# DEGREE_V1_1.net
KiCad netlist of a schematic drawn in EAGLE
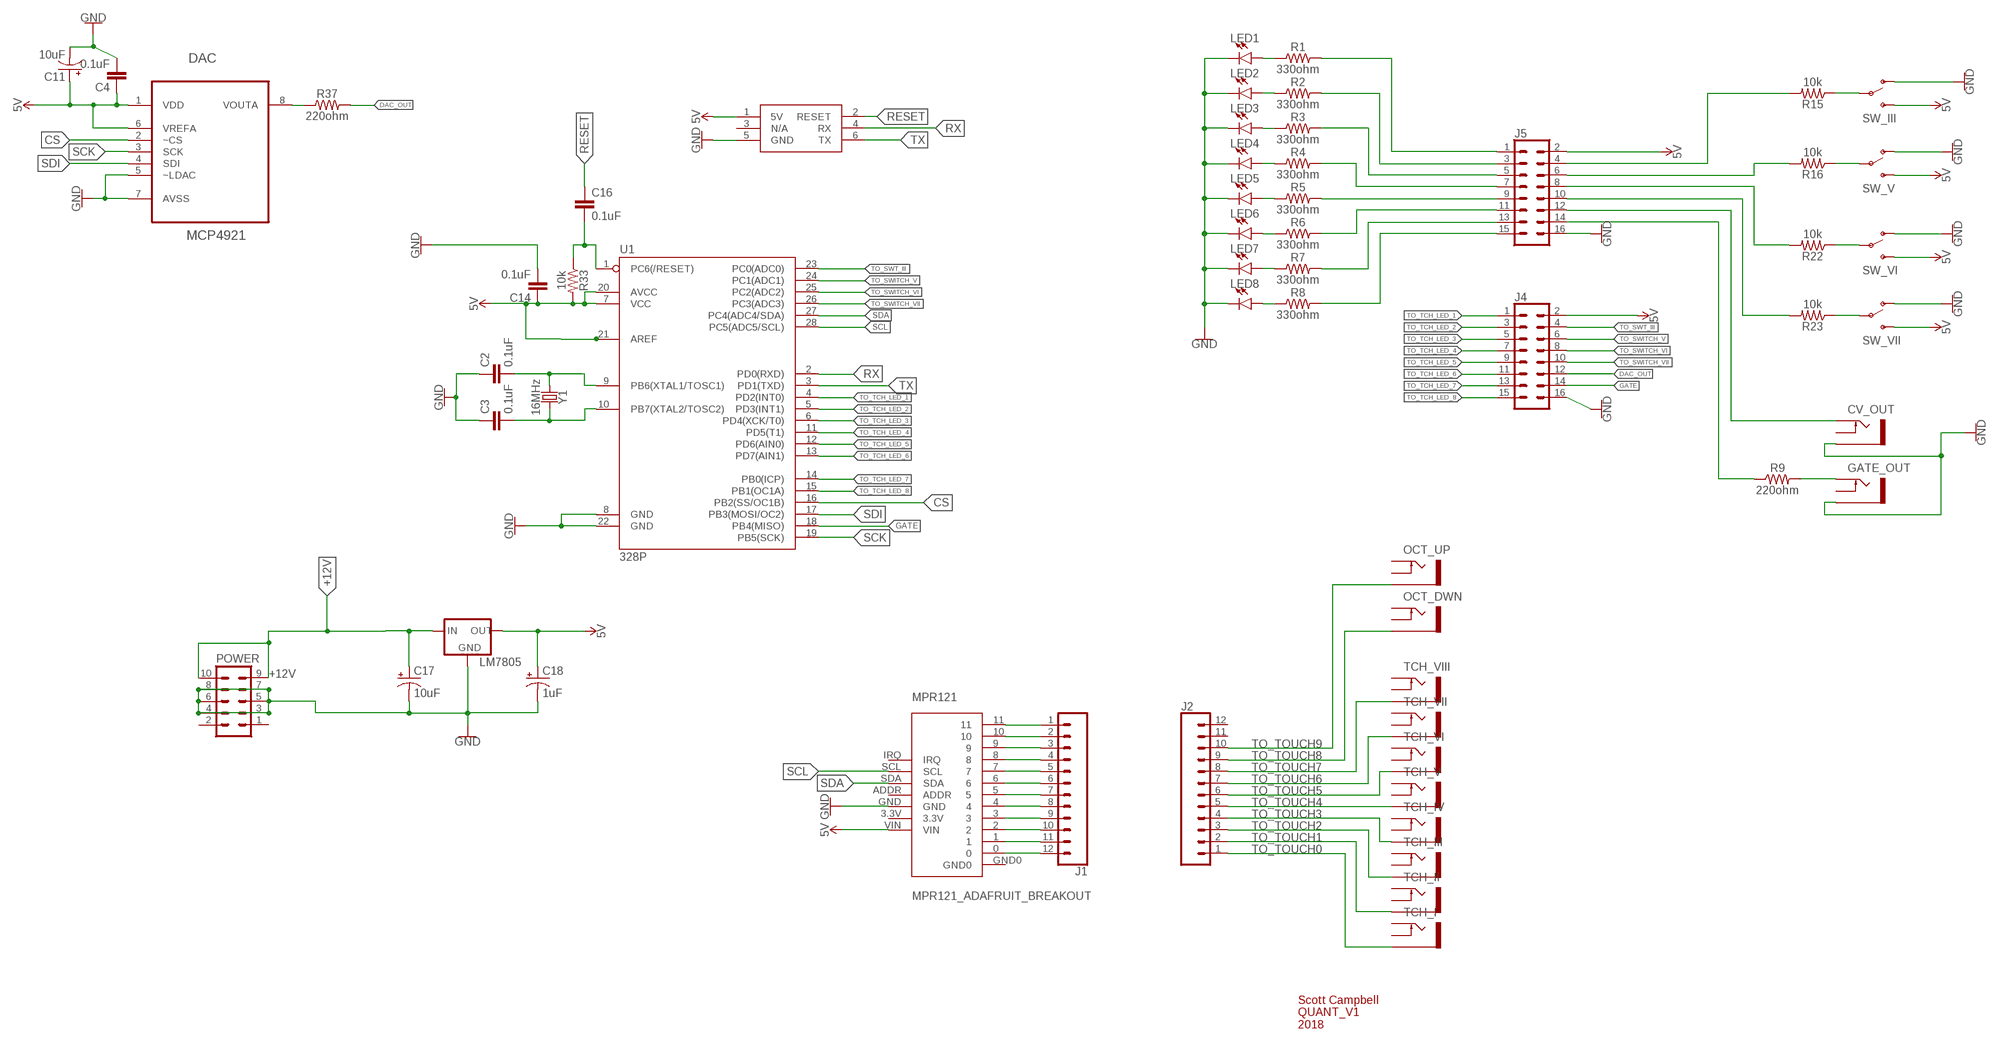
[diagram p0: schematic, sheet 1]

(export (version "E")
  (design (tool "Eeschema 10.0.6"))
  (components
    (comp (ref "C2")
      (value "0.1uF")
      (footprint "eagle-import:CAP-PTH-SMALL-KIT")
      (libsource (lib "eagle-import") (part "0.1UF-KIT-EZ-50V-20%"))
    )
    (comp (ref "C3")
      (value "0.1uF")
      (footprint "eagle-import:CAP-PTH-SMALL-KIT")
      (libsource (lib "eagle-import") (part "0.1UF-KIT-EZ-50V-20%"))
    )
    (comp (ref "C4")
      (value "0.1uF")
      (footprint "eagle-import:CAP-PTH-SMALL-KIT")
      (libsource (lib "eagle-import") (part "0.1UF-KIT-EZ-50V-20%"))
    )
    (comp (ref "C11")
      (value "10uF")
      (footprint "eagle-import:CPOL-RADIAL-2.5MM-5MM")
      (libsource (lib "eagle-import") (part "10UF-POLAR-RADIAL-2.5MM-25V-20%"))
    )
    (comp (ref "C14")
      (value "0.1uF")
      (footprint "eagle-import:CAP-PTH-SMALL-KIT")
      (libsource (lib "eagle-import") (part "0.1UF-KIT-EZ-50V-20%"))
    )
    (comp (ref "C16")
      (value "0.1uF")
      (footprint "eagle-import:CAP-PTH-SMALL-KIT")
      (libsource (lib "eagle-import") (part "0.1UF-KIT-EZ-50V-20%"))
    )
    (comp (ref "C17")
      (value "10uF")
      (footprint "eagle-import:CPOL-RADIAL-2.5MM-5MM")
      (libsource (lib "eagle-import") (part "10UF-POLAR-RADIAL-2.5MM-25V-20%"))
    )
    (comp (ref "C18")
      (value "1uF")
      (footprint "eagle-import:CPOL-RADIAL-2.5MM-5MM")
      (libsource (lib "eagle-import") (part "10UF-POLAR-RADIAL-2.5MM-25V-20%"))
    )
    (comp (ref "CV_OUT")
      (value "CV_OUT")
      (footprint "eagle-import:WQP-PJ301M-12_JACK")
      (libsource (lib "eagle-import") (part "THONKICONNNEW"))
    )
    (comp (ref "DAC")
      (value "MCP4921")
      (footprint "eagle-import:DIP08")
      (libsource (lib "eagle-import") (part "MCP4921"))
    )
    (comp (ref "GATE_OUT")
      (value "GATE_OUT")
      (footprint "eagle-import:WQP-PJ301M-12_JACK")
      (libsource (lib "eagle-import") (part "THONKICONNNEW"))
    )
    (comp (ref "J1")
      (value "CONN_12")
      (footprint "eagle-import:1X12")
      (libsource (lib "eagle-import") (part "CONN_12"))
    )
    (comp (ref "J2")
      (value "CONN_12")
      (footprint "eagle-import:1X12")
      (libsource (lib "eagle-import") (part "CONN_12"))
    )
    (comp (ref "J4")
      (value "CONN_08X2")
      (footprint "eagle-import:2X8")
      (libsource (lib "eagle-import") (part "CONN_08X2"))
    )
    (comp (ref "J5")
      (value "CONN_08X2")
      (footprint "eagle-import:2X8")
      (libsource (lib "eagle-import") (part "CONN_08X2"))
    )
    (comp (ref "LED1")
      (value "LED3MM")
      (footprint "eagle-import:LED_3MM")
      (libsource (lib "eagle-import") (part "LED3MM"))
    )
    (comp (ref "LED2")
      (value "LED3MM")
      (footprint "eagle-import:LED_3MM")
      (libsource (lib "eagle-import") (part "LED3MM"))
    )
    (comp (ref "LED3")
      (value "LED3MM")
      (footprint "eagle-import:LED_3MM")
      (libsource (lib "eagle-import") (part "LED3MM"))
    )
    (comp (ref "LED4")
      (value "LED3MM")
      (footprint "eagle-import:LED_3MM")
      (libsource (lib "eagle-import") (part "LED3MM"))
    )
    (comp (ref "LED5")
      (value "LED3MM")
      (footprint "eagle-import:LED_3MM")
      (libsource (lib "eagle-import") (part "LED3MM"))
    )
    (comp (ref "LED6")
      (value "LED3MM")
      (footprint "eagle-import:LED_3MM")
      (libsource (lib "eagle-import") (part "LED3MM"))
    )
    (comp (ref "LED7")
      (value "LED3MM")
      (footprint "eagle-import:LED_3MM")
      (libsource (lib "eagle-import") (part "LED3MM"))
    )
    (comp (ref "LED8")
      (value "LED3MM")
      (footprint "eagle-import:LED_3MM")
      (libsource (lib "eagle-import") (part "LED3MM"))
    )
    (comp (ref "LM7805")
      (value "V_REG_78XXTO-92_UNTESTED")
      (footprint "eagle-import:TO-92")
      (libsource (lib "eagle-import") (part "V_REG_78XXTO-92_UNTESTED"))
    )
    (comp (ref "MPR121")
      (value "MPR121_ADAFRUIT_BREAKOUT")
      (footprint "eagle-import:MPR121_ADAFRUIT_BREAKOUT")
      (libsource (lib "eagle-import") (part "MPR121_ADAFRUIT_BREAKOUT"))
    )
    (comp (ref "OCT_DWN")
      (value "THONKICONN-ESSY")
      (footprint "eagle-import:THONKICONN-ESSY")
      (libsource (lib "eagle-import") (part "THONKICONN-ESSY"))
    )
    (comp (ref "OCT_UP")
      (value "THONKICONN-ESSY")
      (footprint "eagle-import:THONKICONN-ESSY")
      (libsource (lib "eagle-import") (part "THONKICONN-ESSY"))
    )
    (comp (ref "POWER")
      (value "EURO_POWER_HEADERREGULAR")
      (footprint "eagle-import:EURO_POWER_HEADER")
      (libsource (lib "eagle-import") (part "EURO_POWER_HEADERREGULAR"))
    )
    (comp (ref "R1")
      (value "330ohm")
      (footprint "eagle-import:AXIAL-0.3")
      (libsource (lib "eagle-import") (part "1KOHM-HORIZ-1/4W-5%"))
    )
    (comp (ref "R2")
      (value "330ohm")
      (footprint "eagle-import:AXIAL-0.3")
      (libsource (lib "eagle-import") (part "1KOHM-HORIZ-1/4W-5%"))
    )
    (comp (ref "R3")
      (value "330ohm")
      (footprint "eagle-import:AXIAL-0.3")
      (libsource (lib "eagle-import") (part "1KOHM-HORIZ-1/4W-5%"))
    )
    (comp (ref "R4")
      (value "330ohm")
      (footprint "eagle-import:AXIAL-0.3")
      (libsource (lib "eagle-import") (part "1KOHM-HORIZ-1/4W-5%"))
    )
    (comp (ref "R5")
      (value "330ohm")
      (footprint "eagle-import:AXIAL-0.3")
      (libsource (lib "eagle-import") (part "1KOHM-HORIZ-1/4W-5%"))
    )
    (comp (ref "R6")
      (value "330ohm")
      (footprint "eagle-import:AXIAL-0.3")
      (libsource (lib "eagle-import") (part "1KOHM-HORIZ-1/4W-5%"))
    )
    (comp (ref "R7")
      (value "330ohm")
      (footprint "eagle-import:AXIAL-0.3")
      (libsource (lib "eagle-import") (part "1KOHM-HORIZ-1/4W-5%"))
    )
    (comp (ref "R8")
      (value "330ohm")
      (footprint "eagle-import:AXIAL-0.3")
      (libsource (lib "eagle-import") (part "1KOHM-HORIZ-1/4W-5%"))
    )
    (comp (ref "R9")
      (value "220ohm")
      (footprint "eagle-import:HORIZONTAL_RESISTOR")
      (libsource (lib "eagle-import") (part "RESISTOR_HORZ"))
    )
    (comp (ref "R15")
      (value "10k")
      (footprint "eagle-import:HORIZONTAL_RESISTOR")
      (libsource (lib "eagle-import") (part "RESISTOR_HORZ"))
    )
    (comp (ref "R16")
      (value "10k")
      (footprint "eagle-import:HORIZONTAL_RESISTOR")
      (libsource (lib "eagle-import") (part "RESISTOR_HORZ"))
    )
    (comp (ref "R22")
      (value "10k")
      (footprint "eagle-import:HORIZONTAL_RESISTOR")
      (libsource (lib "eagle-import") (part "RESISTOR_HORZ"))
    )
    (comp (ref "R23")
      (value "10k")
      (footprint "eagle-import:HORIZONTAL_RESISTOR")
      (libsource (lib "eagle-import") (part "RESISTOR_HORZ"))
    )
    (comp (ref "R33")
      (value "10k")
      (footprint "eagle-import:HORIZONTAL_RESISTOR")
      (libsource (lib "eagle-import") (part "RESISTOR_HORZ"))
    )
    (comp (ref "R37")
      (value "220ohm")
      (footprint "eagle-import:VERTICAL_RESISTOR")
      (libsource (lib "eagle-import") (part "RESISTOR_VERT"))
    )
    (comp (ref "SW_III")
      (value "SUBMINI_SPDT")
      (footprint "eagle-import:SUBMINI_TOGGLE")
      (libsource (lib "eagle-import") (part "SUBMINI_SPDT"))
    )
    (comp (ref "SW_V")
      (value "SUBMINI_SPDT")
      (footprint "eagle-import:SUBMINI_TOGGLE")
      (libsource (lib "eagle-import") (part "SUBMINI_SPDT"))
    )
    (comp (ref "SW_VI")
      (value "SUBMINI_SPDT")
      (footprint "eagle-import:SUBMINI_TOGGLE")
      (libsource (lib "eagle-import") (part "SUBMINI_SPDT"))
    )
    (comp (ref "SW_VII")
      (value "SUBMINI_SPDT")
      (footprint "eagle-import:SUBMINI_TOGGLE")
      (libsource (lib "eagle-import") (part "SUBMINI_SPDT"))
    )
    (comp (ref "TCH_I")
      (value "THONKICONN-ESSY")
      (footprint "eagle-import:THONKICONN-ESSY")
      (libsource (lib "eagle-import") (part "THONKICONN-ESSY"))
    )
    (comp (ref "TCH_II")
      (value "THONKICONN-ESSY")
      (footprint "eagle-import:THONKICONN-ESSY")
      (libsource (lib "eagle-import") (part "THONKICONN-ESSY"))
    )
    (comp (ref "TCH_III")
      (value "THONKICONN-ESSY")
      (footprint "eagle-import:THONKICONN-ESSY")
      (libsource (lib "eagle-import") (part "THONKICONN-ESSY"))
    )
    (comp (ref "TCH_IV")
      (value "THONKICONN-ESSY")
      (footprint "eagle-import:THONKICONN-ESSY")
      (libsource (lib "eagle-import") (part "THONKICONN-ESSY"))
    )
    (comp (ref "TCH_V")
      (value "THONKICONN-ESSY")
      (footprint "eagle-import:THONKICONN-ESSY")
      (libsource (lib "eagle-import") (part "THONKICONN-ESSY"))
    )
    (comp (ref "TCH_VI")
      (value "THONKICONN-ESSY")
      (footprint "eagle-import:THONKICONN-ESSY")
      (libsource (lib "eagle-import") (part "THONKICONN-ESSY"))
    )
    (comp (ref "TCH_VII")
      (value "THONKICONN-ESSY")
      (footprint "eagle-import:THONKICONN-ESSY")
      (libsource (lib "eagle-import") (part "THONKICONN-ESSY"))
    )
    (comp (ref "TCH_VIII")
      (value "THONKICONN-ESSY")
      (footprint "eagle-import:THONKICONN-ESSY")
      (libsource (lib "eagle-import") (part "THONKICONN-ESSY"))
    )
    (comp (ref "U$1")
      (value "ATMEGA_PROGRAMMING_PINS")
      (footprint "eagle-import:ATMEGA_PROGRAMMING_PINS")
      (libsource (lib "eagle-import") (part "ATMEGA_PROGRAMMING_PINS"))
    )
    (comp (ref "U1")
      (value "328P")
      (footprint "eagle-import:DIP28")
      (libsource (lib "eagle-import") (part "ATMEGA328P_PDIP"))
    )
    (comp (ref "Y1")
      (value "16MHz")
      (footprint "eagle-import:HC49US")
      (libsource (lib "eagle-import") (part "CRYSTAL-16MHZPTH-HC49US"))
    )
  )
  (nets
    (net (code "1") (name "+12V") (class "Default")
      (node (ref "C17") (pin "1") (pinfunction "+_1") (pintype "passive"))
      (node (ref "LM7805") (pin "3") (pinfunction "IN_3") (pintype "input"))
      (node (ref "POWER") (pin "10") (pinfunction "10_10") (pintype "passive"))
      (node (ref "POWER") (pin "9") (pinfunction "9_9") (pintype "passive"))
    )
    (net (code "2") (name "/TO_TOUCH0") (class "Default")
      (node (ref "J2") (pin "1") (pinfunction "1_1") (pintype "passive"))
      (node (ref "TCH_I") (pin "P$3_SLEEVE") (pinfunction "SLEEVE_P$3_SLEEVE") (pintype "passive"))
    )
    (net (code "3") (name "/TO_TOUCH1") (class "Default")
      (node (ref "J2") (pin "2") (pinfunction "2_2") (pintype "passive"))
      (node (ref "TCH_II") (pin "P$3_SLEEVE") (pinfunction "SLEEVE_P$3_SLEEVE") (pintype "passive"))
    )
    (net (code "4") (name "/TO_TOUCH2") (class "Default")
      (node (ref "J2") (pin "3") (pinfunction "3_3") (pintype "passive"))
      (node (ref "TCH_III") (pin "P$3_SLEEVE") (pinfunction "SLEEVE_P$3_SLEEVE") (pintype "passive"))
    )
    (net (code "5") (name "/TO_TOUCH3") (class "Default")
      (node (ref "J2") (pin "4") (pinfunction "4_4") (pintype "passive"))
      (node (ref "TCH_IV") (pin "P$3_SLEEVE") (pinfunction "SLEEVE_P$3_SLEEVE") (pintype "passive"))
    )
    (net (code "6") (name "/TO_TOUCH4") (class "Default")
      (node (ref "J2") (pin "5") (pinfunction "5_5") (pintype "passive"))
      (node (ref "TCH_V") (pin "P$3_SLEEVE") (pinfunction "SLEEVE_P$3_SLEEVE") (pintype "passive"))
    )
    (net (code "7") (name "/TO_TOUCH5") (class "Default")
      (node (ref "J2") (pin "6") (pinfunction "6_6") (pintype "passive"))
      (node (ref "TCH_VI") (pin "P$3_SLEEVE") (pinfunction "SLEEVE_P$3_SLEEVE") (pintype "passive"))
    )
    (net (code "8") (name "/TO_TOUCH6") (class "Default")
      (node (ref "J2") (pin "7") (pinfunction "7_7") (pintype "passive"))
      (node (ref "TCH_VII") (pin "P$3_SLEEVE") (pinfunction "SLEEVE_P$3_SLEEVE") (pintype "passive"))
    )
    (net (code "9") (name "/TO_TOUCH7") (class "Default")
      (node (ref "J2") (pin "8") (pinfunction "8_8") (pintype "passive"))
      (node (ref "TCH_VIII") (pin "P$3_SLEEVE") (pinfunction "SLEEVE_P$3_SLEEVE") (pintype "passive"))
    )
    (net (code "10") (name "/TO_TOUCH8") (class "Default")
      (node (ref "J2") (pin "9") (pinfunction "9_9") (pintype "passive"))
      (node (ref "OCT_DWN") (pin "P$3_SLEEVE") (pinfunction "SLEEVE_P$3_SLEEVE") (pintype "passive"))
    )
    (net (code "11") (name "/TO_TOUCH9") (class "Default")
      (node (ref "J2") (pin "10") (pinfunction "10_10") (pintype "passive"))
      (node (ref "OCT_UP") (pin "P$3_SLEEVE") (pinfunction "SLEEVE_P$3_SLEEVE") (pintype "passive"))
    )
    (net (code "12") (name "5V") (class "Default")
      (node (ref "C11") (pin "1") (pinfunction "+_1") (pintype "passive"))
      (node (ref "C14") (pin "1") (pinfunction "1_1") (pintype "passive"))
      (node (ref "C18") (pin "1") (pinfunction "+_1") (pintype "passive"))
      (node (ref "C4") (pin "1") (pinfunction "1_1") (pintype "passive"))
      (node (ref "DAC") (pin "1") (pinfunction "VDD_1") (pintype "power_in"))
      (node (ref "DAC") (pin "6") (pinfunction "VREFA_6") (pintype "input"))
      (node (ref "J4") (pin "2") (pinfunction "2_2") (pintype "passive"))
      (node (ref "J5") (pin "2") (pinfunction "2_2") (pintype "passive"))
      (node (ref "LM7805") (pin "1") (pinfunction "OUT_1") (pintype "passive"))
      (node (ref "MPR121") (pin "VIN") (pinfunction "VIN_VIN") (pintype "bidirectional"))
      (node (ref "R33") (pin "2") (pinfunction "2_2") (pintype "passive"))
      (node (ref "SW_III") (pin "3") (pinfunction "S_3") (pintype "passive"))
      (node (ref "SW_V") (pin "3") (pinfunction "S_3") (pintype "passive"))
      (node (ref "SW_VI") (pin "3") (pinfunction "S_3") (pintype "passive"))
      (node (ref "SW_VII") (pin "3") (pinfunction "S_3") (pintype "passive"))
      (node (ref "U$1") (pin "1") (pinfunction "5V_1") (pintype "bidirectional"))
      (node (ref "U1") (pin "20") (pinfunction "AVCC_20") (pintype "bidirectional"))
      (node (ref "U1") (pin "21") (pinfunction "AREF_21") (pintype "bidirectional"))
      (node (ref "U1") (pin "7") (pinfunction "VCC_7") (pintype "bidirectional"))
    )
    (net (code "13") (name "CS") (class "Default")
      (node (ref "DAC") (pin "2") (pinfunction "~{CS}_2") (pintype "input"))
      (node (ref "U1") (pin "16") (pinfunction "PB2(SS/OC1B)_16") (pintype "bidirectional"))
    )
    (net (code "14") (name "DAC_OUT") (class "Default")
      (node (ref "J4") (pin "12") (pinfunction "12_12") (pintype "passive"))
      (node (ref "R37") (pin "2") (pinfunction "2_2") (pintype "passive"))
    )
    (net (code "15") (name "GATE") (class "Default")
      (node (ref "J4") (pin "14") (pinfunction "14_14") (pintype "passive"))
      (node (ref "U1") (pin "18") (pinfunction "PB4(MISO)_18") (pintype "bidirectional"))
    )
    (net (code "16") (name "GND") (class "Default")
      (node (ref "C11") (pin "2") (pinfunction "-_2") (pintype "passive"))
      (node (ref "C14") (pin "2") (pinfunction "2_2") (pintype "passive"))
      (node (ref "C17") (pin "2") (pinfunction "-_2") (pintype "passive"))
      (node (ref "C18") (pin "2") (pinfunction "-_2") (pintype "passive"))
      (node (ref "C2") (pin "1") (pinfunction "1_1") (pintype "passive"))
      (node (ref "C3") (pin "1") (pinfunction "1_1") (pintype "passive"))
      (node (ref "C4") (pin "2") (pinfunction "2_2") (pintype "passive"))
      (node (ref "CV_OUT") (pin "P$3_SLEEVE") (pinfunction "SLEEVE_P$3_SLEEVE") (pintype "passive"))
      (node (ref "DAC") (pin "5") (pinfunction "~{LDAC}_5") (pintype "input"))
      (node (ref "DAC") (pin "7") (pinfunction "AVSS_7") (pintype "passive"))
      (node (ref "GATE_OUT") (pin "P$3_SLEEVE") (pinfunction "SLEEVE_P$3_SLEEVE") (pintype "passive"))
      (node (ref "J4") (pin "16") (pinfunction "16_16") (pintype "passive"))
      (node (ref "J5") (pin "16") (pinfunction "16_16") (pintype "passive"))
      (node (ref "LED1") (pin "K") (pinfunction "C_K") (pintype "passive"))
      (node (ref "LED2") (pin "K") (pinfunction "C_K") (pintype "passive"))
      (node (ref "LED3") (pin "K") (pinfunction "C_K") (pintype "passive"))
      (node (ref "LED4") (pin "K") (pinfunction "C_K") (pintype "passive"))
      (node (ref "LED5") (pin "K") (pinfunction "C_K") (pintype "passive"))
      (node (ref "LED6") (pin "K") (pinfunction "C_K") (pintype "passive"))
      (node (ref "LED7") (pin "K") (pinfunction "C_K") (pintype "passive"))
      (node (ref "LED8") (pin "K") (pinfunction "C_K") (pintype "passive"))
      (node (ref "LM7805") (pin "2") (pinfunction "GND_2") (pintype "input"))
      (node (ref "MPR121") (pin "GND") (pinfunction "GND_GND") (pintype "bidirectional"))
      (node (ref "POWER") (pin "3") (pinfunction "3_3") (pintype "passive"))
      (node (ref "POWER") (pin "4") (pinfunction "4_4") (pintype "passive"))
      (node (ref "POWER") (pin "5") (pinfunction "5_5") (pintype "passive"))
      (node (ref "POWER") (pin "6") (pinfunction "6_6") (pintype "passive"))
      (node (ref "POWER") (pin "7") (pinfunction "7_7") (pintype "passive"))
      (node (ref "POWER") (pin "8") (pinfunction "8_8") (pintype "passive"))
      (node (ref "SW_III") (pin "1") (pinfunction "O_1") (pintype "passive"))
      (node (ref "SW_V") (pin "1") (pinfunction "O_1") (pintype "passive"))
      (node (ref "SW_VI") (pin "1") (pinfunction "O_1") (pintype "passive"))
      (node (ref "SW_VII") (pin "1") (pinfunction "O_1") (pintype "passive"))
      (node (ref "U$1") (pin "5") (pinfunction "GND_5") (pintype "bidirectional"))
      (node (ref "U1") (pin "22") (pinfunction "GND_22") (pintype "bidirectional"))
      (node (ref "U1") (pin "8") (pinfunction "GND_8") (pintype "bidirectional"))
    )
    (net (code "17") (name "Net-(CV_OUT-TIP)") (class "Default")
      (node (ref "CV_OUT") (pin "P$1_TIP") (pinfunction "TIP_P$1_TIP") (pintype "passive"))
      (node (ref "J5") (pin "12") (pinfunction "12_12") (pintype "passive"))
    )
    (net (code "18") (name "Net-(DAC-VOUTA)") (class "Default")
      (node (ref "DAC") (pin "8") (pinfunction "VOUTA_8") (pintype "output"))
      (node (ref "R37") (pin "1") (pinfunction "1_1") (pintype "passive"))
    )
    (net (code "19") (name "Net-(GATE_OUT-TIP)") (class "Default")
      (node (ref "GATE_OUT") (pin "P$1_TIP") (pinfunction "TIP_P$1_TIP") (pintype "passive"))
      (node (ref "R9") (pin "2") (pinfunction "2_2") (pintype "passive"))
    )
    (net (code "20") (name "Net-(J1-Pad1)") (class "Default")
      (node (ref "J1") (pin "1") (pinfunction "1_1") (pintype "passive"))
      (node (ref "MPR121") (pin "11") (pinfunction "11_11") (pintype "bidirectional"))
    )
    (net (code "21") (name "Net-(J1-Pad2)") (class "Default")
      (node (ref "J1") (pin "2") (pinfunction "2_2") (pintype "passive"))
      (node (ref "MPR121") (pin "10") (pinfunction "10_10") (pintype "bidirectional"))
    )
    (net (code "22") (name "Net-(J1-Pad3)") (class "Default")
      (node (ref "J1") (pin "3") (pinfunction "3_3") (pintype "passive"))
      (node (ref "MPR121") (pin "9") (pinfunction "9_9") (pintype "bidirectional"))
    )
    (net (code "23") (name "Net-(J1-Pad4)") (class "Default")
      (node (ref "J1") (pin "4") (pinfunction "4_4") (pintype "passive"))
      (node (ref "MPR121") (pin "8") (pinfunction "8_8") (pintype "bidirectional"))
    )
    (net (code "24") (name "Net-(J1-Pad5)") (class "Default")
      (node (ref "J1") (pin "5") (pinfunction "5_5") (pintype "passive"))
      (node (ref "MPR121") (pin "7") (pinfunction "7_7") (pintype "bidirectional"))
    )
    (net (code "25") (name "Net-(J1-Pad6)") (class "Default")
      (node (ref "J1") (pin "6") (pinfunction "6_6") (pintype "passive"))
      (node (ref "MPR121") (pin "6") (pinfunction "6_6") (pintype "bidirectional"))
    )
    (net (code "26") (name "Net-(J1-Pad7)") (class "Default")
      (node (ref "J1") (pin "7") (pinfunction "7_7") (pintype "passive"))
      (node (ref "MPR121") (pin "5") (pinfunction "5_5") (pintype "bidirectional"))
    )
    (net (code "27") (name "Net-(J1-Pad8)") (class "Default")
      (node (ref "J1") (pin "8") (pinfunction "8_8") (pintype "passive"))
      (node (ref "MPR121") (pin "4") (pinfunction "4_4") (pintype "bidirectional"))
    )
    (net (code "28") (name "Net-(J1-Pad9)") (class "Default")
      (node (ref "J1") (pin "9") (pinfunction "9_9") (pintype "passive"))
      (node (ref "MPR121") (pin "3") (pinfunction "3_3") (pintype "bidirectional"))
    )
    (net (code "29") (name "Net-(J1-Pad10)") (class "Default")
      (node (ref "J1") (pin "10") (pinfunction "10_10") (pintype "passive"))
      (node (ref "MPR121") (pin "2") (pinfunction "2_2") (pintype "bidirectional"))
    )
    (net (code "30") (name "Net-(J1-Pad11)") (class "Default")
      (node (ref "J1") (pin "11") (pinfunction "11_11") (pintype "passive"))
      (node (ref "MPR121") (pin "1") (pinfunction "1_1") (pintype "bidirectional"))
    )
    (net (code "31") (name "Net-(J1-Pad12)") (class "Default")
      (node (ref "J1") (pin "12") (pinfunction "12_12") (pintype "passive"))
      (node (ref "MPR121") (pin "0") (pinfunction "0_0") (pintype "bidirectional"))
    )
    (net (code "32") (name "Net-(J5-Pad4)") (class "Default")
      (node (ref "J5") (pin "4") (pinfunction "4_4") (pintype "passive"))
      (node (ref "R15") (pin "2") (pinfunction "2_2") (pintype "passive"))
    )
    (net (code "33") (name "Net-(J5-Pad6)") (class "Default")
      (node (ref "J5") (pin "6") (pinfunction "6_6") (pintype "passive"))
      (node (ref "R16") (pin "2") (pinfunction "2_2") (pintype "passive"))
    )
    (net (code "34") (name "Net-(J5-Pad8)") (class "Default")
      (node (ref "J5") (pin "8") (pinfunction "8_8") (pintype "passive"))
      (node (ref "R22") (pin "2") (pinfunction "2_2") (pintype "passive"))
    )
    (net (code "35") (name "Net-(J5-Pad10)") (class "Default")
      (node (ref "J5") (pin "10") (pinfunction "10_10") (pintype "passive"))
      (node (ref "R23") (pin "2") (pinfunction "2_2") (pintype "passive"))
    )
    (net (code "36") (name "Net-(J5-Pad14)") (class "Default")
      (node (ref "J5") (pin "14") (pinfunction "14_14") (pintype "passive"))
      (node (ref "R9") (pin "1") (pinfunction "1_1") (pintype "passive"))
    )
    (net (code "37") (name "Net-(R1-1)") (class "Default")
      (node (ref "LED1") (pin "A") (pinfunction "A_A") (pintype "passive"))
      (node (ref "R1") (pin "P$1") (pinfunction "1_P$1") (pintype "passive"))
    )
    (net (code "38") (name "Net-(R1-2)") (class "Default")
      (node (ref "J5") (pin "1") (pinfunction "1_1") (pintype "passive"))
      (node (ref "R1") (pin "P$2") (pinfunction "2_P$2") (pintype "passive"))
    )
    (net (code "39") (name "Net-(R2-1)") (class "Default")
      (node (ref "LED2") (pin "A") (pinfunction "A_A") (pintype "passive"))
      (node (ref "R2") (pin "P$1") (pinfunction "1_P$1") (pintype "passive"))
    )
    (net (code "40") (name "Net-(R2-2)") (class "Default")
      (node (ref "J5") (pin "3") (pinfunction "3_3") (pintype "passive"))
      (node (ref "R2") (pin "P$2") (pinfunction "2_P$2") (pintype "passive"))
    )
    (net (code "41") (name "Net-(R3-1)") (class "Default")
      (node (ref "LED3") (pin "A") (pinfunction "A_A") (pintype "passive"))
      (node (ref "R3") (pin "P$1") (pinfunction "1_P$1") (pintype "passive"))
    )
    (net (code "42") (name "Net-(R3-2)") (class "Default")
      (node (ref "J5") (pin "5") (pinfunction "5_5") (pintype "passive"))
      (node (ref "R3") (pin "P$2") (pinfunction "2_P$2") (pintype "passive"))
    )
    (net (code "43") (name "Net-(R4-1)") (class "Default")
      (node (ref "LED4") (pin "A") (pinfunction "A_A") (pintype "passive"))
      (node (ref "R4") (pin "P$1") (pinfunction "1_P$1") (pintype "passive"))
    )
    (net (code "44") (name "Net-(R4-2)") (class "Default")
      (node (ref "J5") (pin "7") (pinfunction "7_7") (pintype "passive"))
      (node (ref "R4") (pin "P$2") (pinfunction "2_P$2") (pintype "passive"))
    )
    (net (code "45") (name "Net-(R5-1)") (class "Default")
      (node (ref "LED5") (pin "A") (pinfunction "A_A") (pintype "passive"))
      (node (ref "R5") (pin "P$1") (pinfunction "1_P$1") (pintype "passive"))
    )
    (net (code "46") (name "Net-(R5-2)") (class "Default")
      (node (ref "J5") (pin "9") (pinfunction "9_9") (pintype "passive"))
      (node (ref "R5") (pin "P$2") (pinfunction "2_P$2") (pintype "passive"))
    )
    (net (code "47") (name "Net-(R6-1)") (class "Default")
      (node (ref "LED6") (pin "A") (pinfunction "A_A") (pintype "passive"))
      (node (ref "R6") (pin "P$1") (pinfunction "1_P$1") (pintype "passive"))
    )
    (net (code "48") (name "Net-(R6-2)") (class "Default")
      (node (ref "J5") (pin "11") (pinfunction "11_11") (pintype "passive"))
      (node (ref "R6") (pin "P$2") (pinfunction "2_P$2") (pintype "passive"))
    )
    (net (code "49") (name "Net-(R7-1)") (class "Default")
      (node (ref "LED7") (pin "A") (pinfunction "A_A") (pintype "passive"))
      (node (ref "R7") (pin "P$1") (pinfunction "1_P$1") (pintype "passive"))
    )
    (net (code "50") (name "Net-(R7-2)") (class "Default")
      (node (ref "J5") (pin "13") (pinfunction "13_13") (pintype "passive"))
      (node (ref "R7") (pin "P$2") (pinfunction "2_P$2") (pintype "passive"))
    )
    (net (code "51") (name "Net-(R8-1)") (class "Default")
      (node (ref "LED8") (pin "A") (pinfunction "A_A") (pintype "passive"))
      (node (ref "R8") (pin "P$1") (pinfunction "1_P$1") (pintype "passive"))
    )
    (net (code "52") (name "Net-(R8-2)") (class "Default")
      (node (ref "J5") (pin "15") (pinfunction "15_15") (pintype "passive"))
      (node (ref "R8") (pin "P$2") (pinfunction "2_P$2") (pintype "passive"))
    )
    (net (code "53") (name "Net-(SW_III-COMMON)") (class "Default")
      (node (ref "R15") (pin "1") (pinfunction "1_1") (pintype "passive"))
      (node (ref "SW_III") (pin "COM") (pinfunction "COMMON_COM") (pintype "passive"))
    )
    (net (code "54") (name "Net-(SW_V-COMMON)") (class "Default")
      (node (ref "R16") (pin "1") (pinfunction "1_1") (pintype "passive"))
      (node (ref "SW_V") (pin "COM") (pinfunction "COMMON_COM") (pintype "passive"))
    )
    (net (code "55") (name "Net-(SW_VI-COMMON)") (class "Default")
      (node (ref "R22") (pin "1") (pinfunction "1_1") (pintype "passive"))
      (node (ref "SW_VI") (pin "COM") (pinfunction "COMMON_COM") (pintype "passive"))
    )
    (net (code "56") (name "Net-(SW_VII-COMMON)") (class "Default")
      (node (ref "R23") (pin "1") (pinfunction "1_1") (pintype "passive"))
      (node (ref "SW_VII") (pin "COM") (pinfunction "COMMON_COM") (pintype "passive"))
    )
    (net (code "57") (name "Net-(U1-PB6(XTAL1{slash}TOSC1))") (class "Default")
      (node (ref "C2") (pin "2") (pinfunction "2_2") (pintype "passive"))
      (node (ref "U1") (pin "9") (pinfunction "PB6(XTAL1/TOSC1)_9") (pintype "bidirectional"))
      (node (ref "Y1") (pin "1") (pinfunction "1_1") (pintype "passive"))
    )
    (net (code "58") (name "Net-(U1-PB7(XTAL2{slash}TOSC2))") (class "Default")
      (node (ref "C3") (pin "2") (pinfunction "2_2") (pintype "passive"))
      (node (ref "U1") (pin "10") (pinfunction "PB7(XTAL2/TOSC2)_10") (pintype "bidirectional"))
      (node (ref "Y1") (pin "2") (pinfunction "2_2") (pintype "passive"))
    )
    (net (code "59") (name "Net-(U1-PC6({slash}RESET))") (class "Default")
      (node (ref "C16") (pin "2") (pinfunction "2_2") (pintype "passive"))
      (node (ref "R33") (pin "1") (pinfunction "1_1") (pintype "passive"))
      (node (ref "U1") (pin "1") (pinfunction "PC6(/RESET)_1") (pintype "bidirectional"))
    )
    (net (code "60") (name "RESET") (class "Default")
      (node (ref "C16") (pin "1") (pinfunction "1_1") (pintype "passive"))
      (node (ref "U$1") (pin "2") (pinfunction "RESET_2") (pintype "bidirectional"))
    )
    (net (code "61") (name "RX") (class "Default")
      (node (ref "U$1") (pin "4") (pinfunction "RX_4") (pintype "bidirectional"))
      (node (ref "U1") (pin "2") (pinfunction "PD0(RXD)_2") (pintype "bidirectional"))
    )
    (net (code "62") (name "SCK") (class "Default")
      (node (ref "DAC") (pin "3") (pinfunction "SCK_3") (pintype "input"))
      (node (ref "U1") (pin "19") (pinfunction "PB5(SCK)_19") (pintype "bidirectional"))
    )
    (net (code "63") (name "SCL") (class "Default")
      (node (ref "MPR121") (pin "SCL") (pinfunction "SCL_SCL") (pintype "bidirectional"))
      (node (ref "U1") (pin "28") (pinfunction "PC5(ADC5/SCL)_28") (pintype "bidirectional"))
    )
    (net (code "64") (name "SDA") (class "Default")
      (node (ref "MPR121") (pin "SDA") (pinfunction "SDA_SDA") (pintype "bidirectional"))
      (node (ref "U1") (pin "27") (pinfunction "PC4(ADC4/SDA)_27") (pintype "bidirectional"))
    )
    (net (code "65") (name "SDI") (class "Default")
      (node (ref "DAC") (pin "4") (pinfunction "SDI_4") (pintype "input"))
      (node (ref "U1") (pin "17") (pinfunction "PB3(MOSI/OC2)_17") (pintype "bidirectional"))
    )
    (net (code "66") (name "TO_SWITCH_V") (class "Default")
      (node (ref "J4") (pin "6") (pinfunction "6_6") (pintype "passive"))
      (node (ref "U1") (pin "24") (pinfunction "PC1(ADC1)_24") (pintype "bidirectional"))
    )
    (net (code "67") (name "TO_SWITCH_VI") (class "Default")
      (node (ref "J4") (pin "8") (pinfunction "8_8") (pintype "passive"))
      (node (ref "U1") (pin "25") (pinfunction "PC2(ADC2)_25") (pintype "bidirectional"))
    )
    (net (code "68") (name "TO_SWITCH_VII") (class "Default")
      (node (ref "J4") (pin "10") (pinfunction "10_10") (pintype "passive"))
      (node (ref "U1") (pin "26") (pinfunction "PC3(ADC3)_26") (pintype "bidirectional"))
    )
    (net (code "69") (name "TO_SWT_III") (class "Default")
      (node (ref "J4") (pin "4") (pinfunction "4_4") (pintype "passive"))
      (node (ref "U1") (pin "23") (pinfunction "PC0(ADC0)_23") (pintype "bidirectional"))
    )
    (net (code "70") (name "TO_TCH_LED_1") (class "Default")
      (node (ref "J4") (pin "1") (pinfunction "1_1") (pintype "passive"))
      (node (ref "U1") (pin "4") (pinfunction "PD2(INT0)_4") (pintype "bidirectional"))
    )
    (net (code "71") (name "TO_TCH_LED_2") (class "Default")
      (node (ref "J4") (pin "3") (pinfunction "3_3") (pintype "passive"))
      (node (ref "U1") (pin "5") (pinfunction "PD3(INT1)_5") (pintype "bidirectional"))
    )
    (net (code "72") (name "TO_TCH_LED_3") (class "Default")
      (node (ref "J4") (pin "5") (pinfunction "5_5") (pintype "passive"))
      (node (ref "U1") (pin "6") (pinfunction "PD4(XCK/T0)_6") (pintype "bidirectional"))
    )
    (net (code "73") (name "TO_TCH_LED_4") (class "Default")
      (node (ref "J4") (pin "7") (pinfunction "7_7") (pintype "passive"))
      (node (ref "U1") (pin "11") (pinfunction "PD5(T1)_11") (pintype "bidirectional"))
    )
    (net (code "74") (name "TO_TCH_LED_5") (class "Default")
      (node (ref "J4") (pin "9") (pinfunction "9_9") (pintype "passive"))
      (node (ref "U1") (pin "12") (pinfunction "PD6(AIN0)_12") (pintype "bidirectional"))
    )
    (net (code "75") (name "TO_TCH_LED_6") (class "Default")
      (node (ref "J4") (pin "11") (pinfunction "11_11") (pintype "passive"))
      (node (ref "U1") (pin "13") (pinfunction "PD7(AIN1)_13") (pintype "bidirectional"))
    )
    (net (code "76") (name "TO_TCH_LED_7") (class "Default")
      (node (ref "J4") (pin "13") (pinfunction "13_13") (pintype "passive"))
      (node (ref "U1") (pin "14") (pinfunction "PB0(ICP)_14") (pintype "bidirectional"))
    )
    (net (code "77") (name "TO_TCH_LED_8") (class "Default")
      (node (ref "J4") (pin "15") (pinfunction "15_15") (pintype "passive"))
      (node (ref "U1") (pin "15") (pinfunction "PB1(OC1A)_15") (pintype "bidirectional"))
    )
    (net (code "78") (name "TX") (class "Default")
      (node (ref "U$1") (pin "6") (pinfunction "TX_6") (pintype "bidirectional"))
      (node (ref "U1") (pin "3") (pinfunction "PD1(TXD)_3") (pintype "bidirectional"))
    )
    (net (code "79") (name "unconnected-(CV_OUT-SWITCH-PadP$2_SWITCH)") (class "Default")
      (node (ref "CV_OUT") (pin "P$2_SWITCH") (pinfunction "SWITCH_P$2_SWITCH") (pintype "passive"))
    )
    (net (code "80") (name "unconnected-(GATE_OUT-SWITCH-PadP$2_SWITCH)") (class "Default")
      (node (ref "GATE_OUT") (pin "P$2_SWITCH") (pinfunction "SWITCH_P$2_SWITCH") (pintype "passive"))
    )
    (net (code "81") (name "unconnected-(J2-Pad11)") (class "Default")
      (node (ref "J2") (pin "11") (pinfunction "11_11") (pintype "passive"))
    )
    (net (code "82") (name "unconnected-(J2-Pad12)") (class "Default")
      (node (ref "J2") (pin "12") (pinfunction "12_12") (pintype "passive"))
    )
    (net (code "83") (name "unconnected-(MPR121-Pad3.3V)") (class "Default")
      (node (ref "MPR121") (pin "3.3V") (pinfunction "3.3V_3.3V") (pintype "bidirectional"))
    )
    (net (code "84") (name "unconnected-(MPR121-PadADDR)") (class "Default")
      (node (ref "MPR121") (pin "ADDR") (pinfunction "ADDR_ADDR") (pintype "bidirectional"))
    )
    (net (code "85") (name "unconnected-(MPR121-PadGND0)") (class "Default")
      (node (ref "MPR121") (pin "GND0") (pinfunction "GND0_GND0") (pintype "bidirectional"))
    )
    (net (code "86") (name "unconnected-(MPR121-PadIRQ)") (class "Default")
      (node (ref "MPR121") (pin "IRQ") (pinfunction "IRQ_IRQ") (pintype "bidirectional"))
    )
    (net (code "87") (name "unconnected-(OCT_DWN-SWITCH-PadP$2_SWITCH)") (class "Default")
      (node (ref "OCT_DWN") (pin "P$2_SWITCH") (pinfunction "SWITCH_P$2_SWITCH") (pintype "passive"))
    )
    (net (code "88") (name "unconnected-(OCT_DWN-TIP-PadP$1_TIP)") (class "Default")
      (node (ref "OCT_DWN") (pin "P$1_TIP") (pinfunction "TIP_P$1_TIP") (pintype "passive"))
    )
    (net (code "89") (name "unconnected-(OCT_UP-SWITCH-PadP$2_SWITCH)") (class "Default")
      (node (ref "OCT_UP") (pin "P$2_SWITCH") (pinfunction "SWITCH_P$2_SWITCH") (pintype "passive"))
    )
    (net (code "90") (name "unconnected-(OCT_UP-TIP-PadP$1_TIP)") (class "Default")
      (node (ref "OCT_UP") (pin "P$1_TIP") (pinfunction "TIP_P$1_TIP") (pintype "passive"))
    )
    (net (code "91") (name "unconnected-(POWER-Pad1)") (class "Default")
      (node (ref "POWER") (pin "1") (pinfunction "1_1") (pintype "passive"))
    )
    (net (code "92") (name "unconnected-(POWER-Pad2)") (class "Default")
      (node (ref "POWER") (pin "2") (pinfunction "2_2") (pintype "passive"))
    )
    (net (code "93") (name "unconnected-(TCH_I-SWITCH-PadP$2_SWITCH)") (class "Default")
      (node (ref "TCH_I") (pin "P$2_SWITCH") (pinfunction "SWITCH_P$2_SWITCH") (pintype "passive"))
    )
    (net (code "94") (name "unconnected-(TCH_I-TIP-PadP$1_TIP)") (class "Default")
      (node (ref "TCH_I") (pin "P$1_TIP") (pinfunction "TIP_P$1_TIP") (pintype "passive"))
    )
    (net (code "95") (name "unconnected-(TCH_II-SWITCH-PadP$2_SWITCH)") (class "Default")
      (node (ref "TCH_II") (pin "P$2_SWITCH") (pinfunction "SWITCH_P$2_SWITCH") (pintype "passive"))
    )
    (net (code "96") (name "unconnected-(TCH_II-TIP-PadP$1_TIP)") (class "Default")
      (node (ref "TCH_II") (pin "P$1_TIP") (pinfunction "TIP_P$1_TIP") (pintype "passive"))
    )
    (net (code "97") (name "unconnected-(TCH_III-SWITCH-PadP$2_SWITCH)") (class "Default")
      (node (ref "TCH_III") (pin "P$2_SWITCH") (pinfunction "SWITCH_P$2_SWITCH") (pintype "passive"))
    )
    (net (code "98") (name "unconnected-(TCH_III-TIP-PadP$1_TIP)") (class "Default")
      (node (ref "TCH_III") (pin "P$1_TIP") (pinfunction "TIP_P$1_TIP") (pintype "passive"))
    )
    (net (code "99") (name "unconnected-(TCH_IV-SWITCH-PadP$2_SWITCH)") (class "Default")
      (node (ref "TCH_IV") (pin "P$2_SWITCH") (pinfunction "SWITCH_P$2_SWITCH") (pintype "passive"))
    )
    (net (code "100") (name "unconnected-(TCH_IV-TIP-PadP$1_TIP)") (class "Default")
      (node (ref "TCH_IV") (pin "P$1_TIP") (pinfunction "TIP_P$1_TIP") (pintype "passive"))
    )
    (net (code "101") (name "unconnected-(TCH_V-SWITCH-PadP$2_SWITCH)") (class "Default")
      (node (ref "TCH_V") (pin "P$2_SWITCH") (pinfunction "SWITCH_P$2_SWITCH") (pintype "passive"))
    )
    (net (code "102") (name "unconnected-(TCH_V-TIP-PadP$1_TIP)") (class "Default")
      (node (ref "TCH_V") (pin "P$1_TIP") (pinfunction "TIP_P$1_TIP") (pintype "passive"))
    )
    (net (code "103") (name "unconnected-(TCH_VI-SWITCH-PadP$2_SWITCH)") (class "Default")
      (node (ref "TCH_VI") (pin "P$2_SWITCH") (pinfunction "SWITCH_P$2_SWITCH") (pintype "passive"))
    )
    (net (code "104") (name "unconnected-(TCH_VI-TIP-PadP$1_TIP)") (class "Default")
      (node (ref "TCH_VI") (pin "P$1_TIP") (pinfunction "TIP_P$1_TIP") (pintype "passive"))
    )
    (net (code "105") (name "unconnected-(TCH_VII-SWITCH-PadP$2_SWITCH)") (class "Default")
      (node (ref "TCH_VII") (pin "P$2_SWITCH") (pinfunction "SWITCH_P$2_SWITCH") (pintype "passive"))
    )
    (net (code "106") (name "unconnected-(TCH_VII-TIP-PadP$1_TIP)") (class "Default")
      (node (ref "TCH_VII") (pin "P$1_TIP") (pinfunction "TIP_P$1_TIP") (pintype "passive"))
    )
    (net (code "107") (name "unconnected-(TCH_VIII-SWITCH-PadP$2_SWITCH)") (class "Default")
      (node (ref "TCH_VIII") (pin "P$2_SWITCH") (pinfunction "SWITCH_P$2_SWITCH") (pintype "passive"))
    )
    (net (code "108") (name "unconnected-(TCH_VIII-TIP-PadP$1_TIP)") (class "Default")
      (node (ref "TCH_VIII") (pin "P$1_TIP") (pinfunction "TIP_P$1_TIP") (pintype "passive"))
    )
    (net (code "109") (name "unconnected-(U$1-N{slash}A-Pad3)") (class "Default")
      (node (ref "U$1") (pin "3") (pinfunction "N/A_3") (pintype "bidirectional"))
    )
  )
)
